# power.net
KiCad netlist of a schematic drawn in Altium Designer
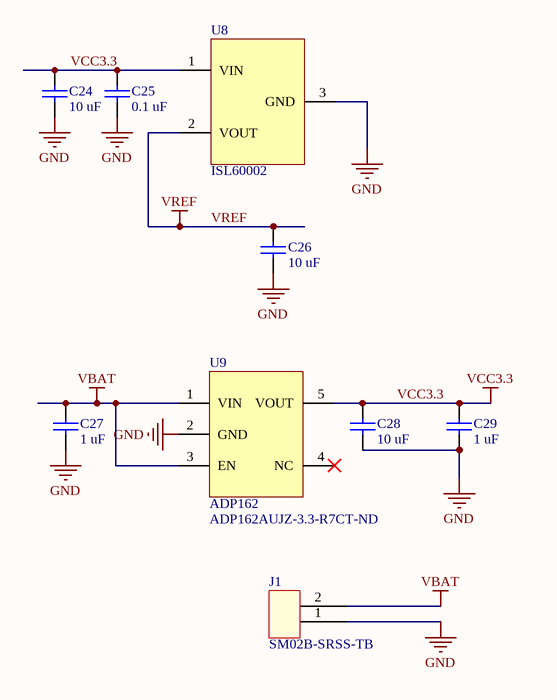
[diagram p0: power.SchDoc]

(export (version "E")
  (design (tool "Eeschema 10.0.6"))
  (components
    (comp (ref "C24")
      (value "10 uF")
      (footprint "0603")
      (description "Ceramic capacitor, 10 uF, 0603 package")
      (fields (field (name "TOLERANCE") "20%") (field (name "Comment") "Ceramic capacitor"))
      (libsource (lib "rlc") (part "C_10u_0603_ceramic"))
    )
    (comp (ref "C25")
      (value "0.1 uF")
      (footprint "0402")
      (description "Ceramic capacitor, 0.1u, 0402 package")
      (fields (field (name "TOLERANCE") "10%") (field (name "Comment") "Ceramic capacitor"))
      (libsource (lib "rlc") (part "C_0.1u_0402_ceramic"))
    )
    (comp (ref "C26")
      (value "10 uF")
      (footprint "0603")
      (description "Ceramic capacitor, 10 uF, 0603 package")
      (fields (field (name "TOLERANCE") "20%") (field (name "Comment") "Ceramic capacitor"))
      (libsource (lib "rlc") (part "C_10u_0603_ceramic"))
    )
    (comp (ref "C27")
      (value "1 uF")
      (footprint "0402")
      (description "Ceramic capacitor, 1 uF, 0402 package")
      (fields (field (name "TOLERANCE") "10%") (field (name "Comment") "Ceramic capacitor"))
      (libsource (lib "rlc") (part "C_1u_0402_ceramic"))
    )
    (comp (ref "C28")
      (value "10 uF")
      (footprint "0603")
      (description "Ceramic capacitor, 10 uF, 0603 package")
      (fields (field (name "TOLERANCE") "20%") (field (name "Comment") "Ceramic capacitor"))
      (libsource (lib "rlc") (part "C_10u_0603_ceramic"))
    )
    (comp (ref "C29")
      (value "1 uF")
      (footprint "0402")
      (description "Ceramic capacitor, 1 uF, 0402 package")
      (fields (field (name "TOLERANCE") "10%") (field (name "Comment") "Ceramic capacitor"))
      (libsource (lib "rlc") (part "C_1u_0402_ceramic"))
    )
    (comp (ref "J1")
      (value "SM02B-SRSS-TB")
      (footprint "JST SH series")
      (description "CONN HEADER SH 2POS SIDE 1MM TIN")
      (libsource (lib "opo") (part "SM02B-SRSS-TB"))
    )
    (comp (ref "U8")
      (value "ISL60002")
      (footprint "SOT23-3N")
      (description "IC VREF SERIES PREC SOT-23-3")
      (libsource (lib "opo") (part "ISL60002"))
    )
    (comp (ref "U9")
      (value "ADP162")
      (footprint "TSOT23-5")
      (description "Ultralow Quiescent Current,  150 mA, CMOS Linear Regulators")
      (fields (field (name "SUPPLIER PART NUMBER 1") "ADP162AUJZ-3.3-R7CT-ND"))
      (libsource (lib "opo") (part "ADP162"))
    )
  )
  (nets
    (net (code "1") (name "GND") (class "Default")
      (node (ref "C24") (pin "2") (pintype "passive"))
      (node (ref "C25") (pin "2") (pintype "passive"))
      (node (ref "C26") (pin "2") (pintype "passive"))
      (node (ref "C27") (pin "2") (pintype "passive"))
      (node (ref "C28") (pin "2") (pintype "passive"))
      (node (ref "C29") (pin "2") (pintype "passive"))
      (node (ref "J1") (pin "1") (pinfunction "1_1") (pintype "passive"))
      (node (ref "U8") (pin "3") (pinfunction "GND_3") (pintype "passive"))
      (node (ref "U9") (pin "2") (pinfunction "GND_2") (pintype "passive"))
    )
    (net (code "2") (name "VBAT") (class "Default")
      (node (ref "C27") (pin "1") (pintype "passive"))
      (node (ref "J1") (pin "2") (pinfunction "2_2") (pintype "passive"))
      (node (ref "U9") (pin "1") (pinfunction "VIN_1") (pintype "passive"))
      (node (ref "U9") (pin "3") (pinfunction "EN_3") (pintype "passive"))
    )
    (net (code "3") (name "VCC3.3") (class "Default")
      (node (ref "C24") (pin "1") (pintype "passive"))
      (node (ref "C25") (pin "1") (pintype "passive"))
      (node (ref "C28") (pin "1") (pintype "passive"))
      (node (ref "C29") (pin "1") (pintype "passive"))
      (node (ref "U8") (pin "1") (pinfunction "VIN_1") (pintype "passive"))
      (node (ref "U9") (pin "5") (pinfunction "VOUT_5") (pintype "passive"))
    )
    (net (code "4") (name "VREF") (class "Default")
      (node (ref "C26") (pin "1") (pintype "passive"))
      (node (ref "U8") (pin "2") (pinfunction "VOUT_2") (pintype "passive"))
    )
    (net (code "5") (name "unconnected-(U9-NC-Pad4)") (class "Default")
      (node (ref "U9") (pin "4") (pinfunction "NC_4") (pintype "passive+no_connect"))
    )
  )
)
